# prototype_v2.net
KiCad netlist of a schematic drawn in EAGLE
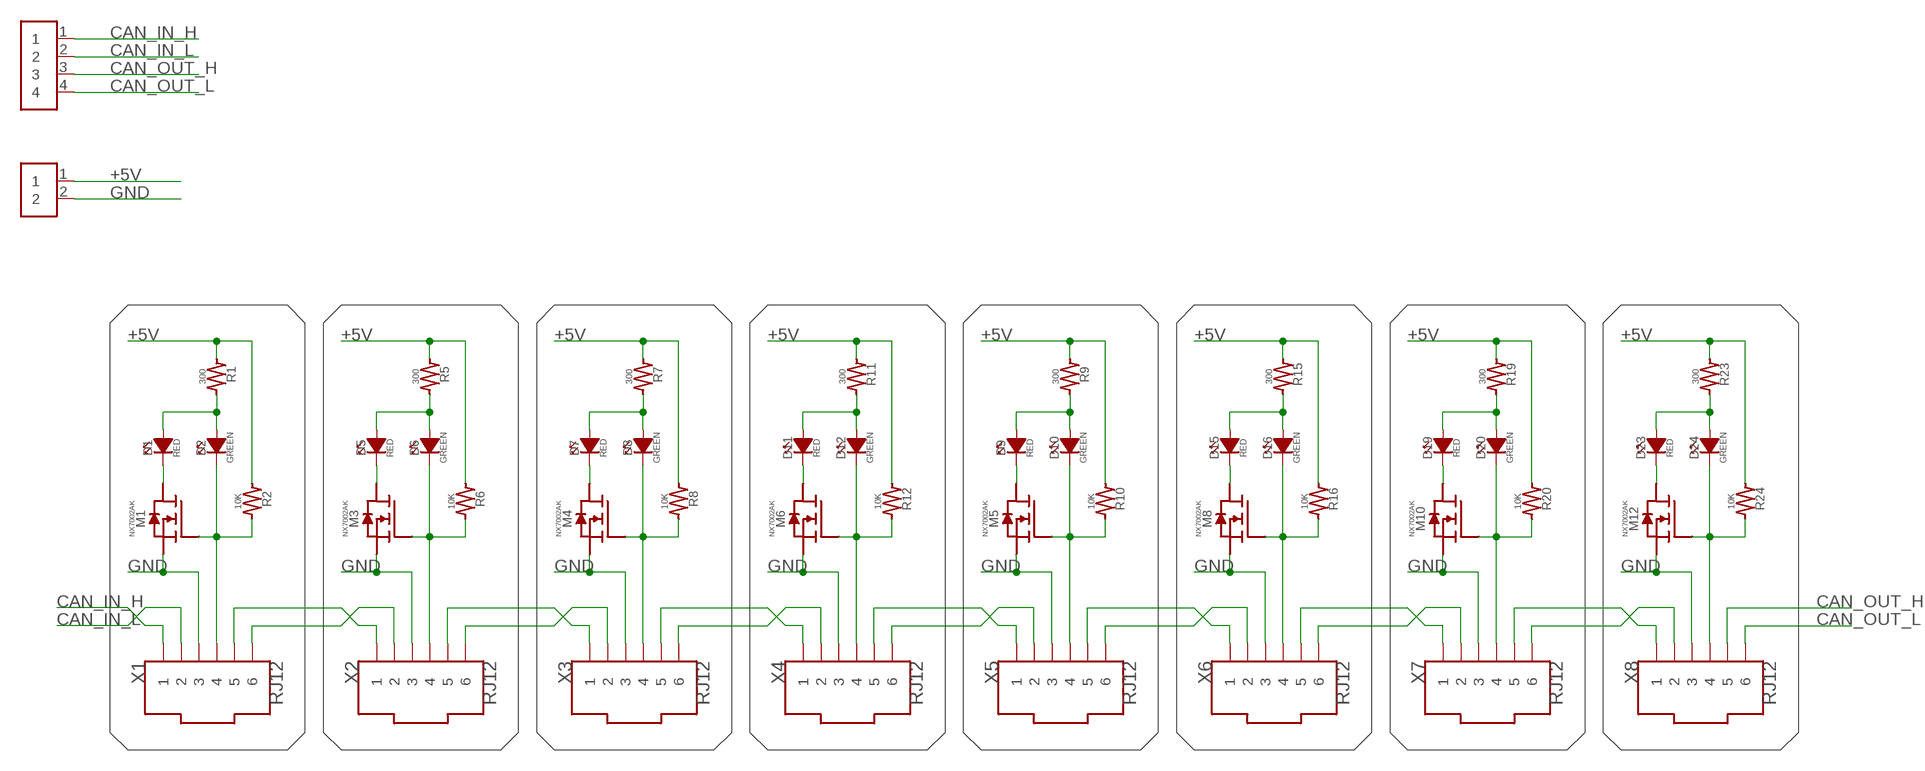
[diagram p0: schematic, sheet 1]

(export (version "E")
  (design (tool "Eeschema 10.0.6"))
  (components
    (comp (ref "D1")
      (value "RED")
      (footprint "eagle-import:0603-LED")
      (libsource (lib "eagle-import") (part "LED"))
    )
    (comp (ref "D2")
      (value "GREEN")
      (footprint "eagle-import:0603-LED")
      (libsource (lib "eagle-import") (part "LED"))
    )
    (comp (ref "D5")
      (value "RED")
      (footprint "eagle-import:0603-LED")
      (libsource (lib "eagle-import") (part "LED"))
    )
    (comp (ref "D6")
      (value "GREEN")
      (footprint "eagle-import:0603-LED")
      (libsource (lib "eagle-import") (part "LED"))
    )
    (comp (ref "D7")
      (value "RED")
      (footprint "eagle-import:0603-LED")
      (libsource (lib "eagle-import") (part "LED"))
    )
    (comp (ref "D8")
      (value "GREEN")
      (footprint "eagle-import:0603-LED")
      (libsource (lib "eagle-import") (part "LED"))
    )
    (comp (ref "D9")
      (value "RED")
      (footprint "eagle-import:0603-LED")
      (libsource (lib "eagle-import") (part "LED"))
    )
    (comp (ref "D10")
      (value "GREEN")
      (footprint "eagle-import:0603-LED")
      (libsource (lib "eagle-import") (part "LED"))
    )
    (comp (ref "D11")
      (value "RED")
      (footprint "eagle-import:0603-LED")
      (libsource (lib "eagle-import") (part "LED"))
    )
    (comp (ref "D12")
      (value "GREEN")
      (footprint "eagle-import:0603-LED")
      (libsource (lib "eagle-import") (part "LED"))
    )
    (comp (ref "D15")
      (value "RED")
      (footprint "eagle-import:0603-LED")
      (libsource (lib "eagle-import") (part "LED"))
    )
    (comp (ref "D16")
      (value "GREEN")
      (footprint "eagle-import:0603-LED")
      (libsource (lib "eagle-import") (part "LED"))
    )
    (comp (ref "D19")
      (value "RED")
      (footprint "eagle-import:0603-LED")
      (libsource (lib "eagle-import") (part "LED"))
    )
    (comp (ref "D20")
      (value "GREEN")
      (footprint "eagle-import:0603-LED")
      (libsource (lib "eagle-import") (part "LED"))
    )
    (comp (ref "D23")
      (value "RED")
      (footprint "eagle-import:0603-LED")
      (libsource (lib "eagle-import") (part "LED"))
    )
    (comp (ref "D24")
      (value "GREEN")
      (footprint "eagle-import:0603-LED")
      (libsource (lib "eagle-import") (part "LED"))
    )
    (comp (ref "M1")
      (value "NX7002AK")
      (footprint "eagle-import:SOT-23")
      (libsource (lib "eagle-import") (part "N-FET"))
    )
    (comp (ref "M3")
      (value "NX7002AK")
      (footprint "eagle-import:SOT-23")
      (libsource (lib "eagle-import") (part "N-FET"))
    )
    (comp (ref "M4")
      (value "NX7002AK")
      (footprint "eagle-import:SOT-23")
      (libsource (lib "eagle-import") (part "N-FET"))
    )
    (comp (ref "M5")
      (value "NX7002AK")
      (footprint "eagle-import:SOT-23")
      (libsource (lib "eagle-import") (part "N-FET"))
    )
    (comp (ref "M6")
      (value "NX7002AK")
      (footprint "eagle-import:SOT-23")
      (libsource (lib "eagle-import") (part "N-FET"))
    )
    (comp (ref "M8")
      (value "NX7002AK")
      (footprint "eagle-import:SOT-23")
      (libsource (lib "eagle-import") (part "N-FET"))
    )
    (comp (ref "M10")
      (value "NX7002AK")
      (footprint "eagle-import:SOT-23")
      (libsource (lib "eagle-import") (part "N-FET"))
    )
    (comp (ref "M12")
      (value "NX7002AK")
      (footprint "eagle-import:SOT-23")
      (libsource (lib "eagle-import") (part "N-FET"))
    )
    (comp (ref "R1")
      (value "300")
      (footprint "eagle-import:0603")
      (libsource (lib "eagle-import") (part "RESISTOR0603"))
    )
    (comp (ref "R2")
      (value "10K")
      (footprint "eagle-import:0603")
      (libsource (lib "eagle-import") (part "RESISTOR0603"))
    )
    (comp (ref "R5")
      (value "300")
      (footprint "eagle-import:0603")
      (libsource (lib "eagle-import") (part "RESISTOR0603"))
    )
    (comp (ref "R6")
      (value "10K")
      (footprint "eagle-import:0603")
      (libsource (lib "eagle-import") (part "RESISTOR0603"))
    )
    (comp (ref "R7")
      (value "300")
      (footprint "eagle-import:0603")
      (libsource (lib "eagle-import") (part "RESISTOR0603"))
    )
    (comp (ref "R8")
      (value "10K")
      (footprint "eagle-import:0603")
      (libsource (lib "eagle-import") (part "RESISTOR0603"))
    )
    (comp (ref "R9")
      (value "300")
      (footprint "eagle-import:0603")
      (libsource (lib "eagle-import") (part "RESISTOR0603"))
    )
    (comp (ref "R10")
      (value "10K")
      (footprint "eagle-import:0603")
      (libsource (lib "eagle-import") (part "RESISTOR0603"))
    )
    (comp (ref "R11")
      (value "300")
      (footprint "eagle-import:0603")
      (libsource (lib "eagle-import") (part "RESISTOR0603"))
    )
    (comp (ref "R12")
      (value "10K")
      (footprint "eagle-import:0603")
      (libsource (lib "eagle-import") (part "RESISTOR0603"))
    )
    (comp (ref "R15")
      (value "300")
      (footprint "eagle-import:0603")
      (libsource (lib "eagle-import") (part "RESISTOR0603"))
    )
    (comp (ref "R16")
      (value "10K")
      (footprint "eagle-import:0603")
      (libsource (lib "eagle-import") (part "RESISTOR0603"))
    )
    (comp (ref "R19")
      (value "300")
      (footprint "eagle-import:0603")
      (libsource (lib "eagle-import") (part "RESISTOR0603"))
    )
    (comp (ref "R20")
      (value "10K")
      (footprint "eagle-import:0603")
      (libsource (lib "eagle-import") (part "RESISTOR0603"))
    )
    (comp (ref "R23")
      (value "300")
      (footprint "eagle-import:0603")
      (libsource (lib "eagle-import") (part "RESISTOR0603"))
    )
    (comp (ref "R24")
      (value "10K")
      (footprint "eagle-import:0603")
      (libsource (lib "eagle-import") (part "RESISTOR0603"))
    )
    (comp (ref "U$1")
      (value "TERMINAL_BLOCK")
      (footprint "eagle-import:TERMINALBLOCK-4")
      (libsource (lib "eagle-import") (part "TERMINAL_BLOCK"))
    )
    (comp (ref "U$2")
      (value "POWER_BLOCK")
      (footprint "eagle-import:TERMINALBLOCK-2")
      (libsource (lib "eagle-import") (part "POWER_BLOCK"))
    )
    (comp (ref "X1")
      (value "RJ12")
      (footprint "eagle-import:RJ12")
      (libsource (lib "eagle-import") (part "RJ12"))
    )
    (comp (ref "X2")
      (value "RJ12")
      (footprint "eagle-import:RJ12")
      (libsource (lib "eagle-import") (part "RJ12"))
    )
    (comp (ref "X3")
      (value "RJ12")
      (footprint "eagle-import:RJ12")
      (libsource (lib "eagle-import") (part "RJ12"))
    )
    (comp (ref "X4")
      (value "RJ12")
      (footprint "eagle-import:RJ12")
      (libsource (lib "eagle-import") (part "RJ12"))
    )
    (comp (ref "X5")
      (value "RJ12")
      (footprint "eagle-import:RJ12")
      (libsource (lib "eagle-import") (part "RJ12"))
    )
    (comp (ref "X6")
      (value "RJ12")
      (footprint "eagle-import:RJ12")
      (libsource (lib "eagle-import") (part "RJ12"))
    )
    (comp (ref "X7")
      (value "RJ12")
      (footprint "eagle-import:RJ12")
      (libsource (lib "eagle-import") (part "RJ12"))
    )
    (comp (ref "X8")
      (value "RJ12")
      (footprint "eagle-import:RJ12")
      (libsource (lib "eagle-import") (part "RJ12"))
    )
  )
  (nets
    (net (code "1") (name "/+5V") (class "Default")
      (node (ref "R1") (pin "1") (pinfunction "1_1") (pintype "bidirectional"))
      (node (ref "R10") (pin "1") (pinfunction "1_1") (pintype "bidirectional"))
      (node (ref "R11") (pin "1") (pinfunction "1_1") (pintype "bidirectional"))
      (node (ref "R12") (pin "1") (pinfunction "1_1") (pintype "bidirectional"))
      (node (ref "R15") (pin "1") (pinfunction "1_1") (pintype "bidirectional"))
      (node (ref "R16") (pin "1") (pinfunction "1_1") (pintype "bidirectional"))
      (node (ref "R19") (pin "1") (pinfunction "1_1") (pintype "bidirectional"))
      (node (ref "R2") (pin "1") (pinfunction "1_1") (pintype "bidirectional"))
      (node (ref "R20") (pin "1") (pinfunction "1_1") (pintype "bidirectional"))
      (node (ref "R23") (pin "1") (pinfunction "1_1") (pintype "bidirectional"))
      (node (ref "R24") (pin "1") (pinfunction "1_1") (pintype "bidirectional"))
      (node (ref "R5") (pin "1") (pinfunction "1_1") (pintype "bidirectional"))
      (node (ref "R6") (pin "1") (pinfunction "1_1") (pintype "bidirectional"))
      (node (ref "R7") (pin "1") (pinfunction "1_1") (pintype "bidirectional"))
      (node (ref "R8") (pin "1") (pinfunction "1_1") (pintype "bidirectional"))
      (node (ref "R9") (pin "1") (pinfunction "1_1") (pintype "bidirectional"))
      (node (ref "U$2") (pin "1") (pinfunction "1_1") (pintype "bidirectional"))
    )
    (net (code "2") (name "/CAN_IN_H") (class "Default")
      (node (ref "U$1") (pin "1") (pinfunction "1_1") (pintype "bidirectional"))
      (node (ref "X1") (pin "1") (pinfunction "1_1") (pintype "bidirectional"))
    )
    (net (code "3") (name "/CAN_IN_L") (class "Default")
      (node (ref "U$1") (pin "2") (pinfunction "2_2") (pintype "bidirectional"))
      (node (ref "X1") (pin "2") (pinfunction "2_2") (pintype "bidirectional"))
    )
    (net (code "4") (name "/CAN_OUT_H") (class "Default")
      (node (ref "U$1") (pin "3") (pinfunction "3_3") (pintype "bidirectional"))
      (node (ref "X8") (pin "5") (pinfunction "5_5") (pintype "bidirectional"))
    )
    (net (code "5") (name "/CAN_OUT_L") (class "Default")
      (node (ref "U$1") (pin "4") (pinfunction "4_4") (pintype "bidirectional"))
      (node (ref "X8") (pin "6") (pinfunction "6_6") (pintype "bidirectional"))
    )
    (net (code "6") (name "/GND") (class "Default")
      (node (ref "M1") (pin "2") (pinfunction "SOURCE_2") (pintype "bidirectional"))
      (node (ref "M10") (pin "2") (pinfunction "SOURCE_2") (pintype "bidirectional"))
      (node (ref "M12") (pin "2") (pinfunction "SOURCE_2") (pintype "bidirectional"))
      (node (ref "M3") (pin "2") (pinfunction "SOURCE_2") (pintype "bidirectional"))
      (node (ref "M4") (pin "2") (pinfunction "SOURCE_2") (pintype "bidirectional"))
      (node (ref "M5") (pin "2") (pinfunction "SOURCE_2") (pintype "bidirectional"))
      (node (ref "M6") (pin "2") (pinfunction "SOURCE_2") (pintype "bidirectional"))
      (node (ref "M8") (pin "2") (pinfunction "SOURCE_2") (pintype "bidirectional"))
      (node (ref "U$2") (pin "2") (pinfunction "2_2") (pintype "bidirectional"))
      (node (ref "X1") (pin "3") (pinfunction "3_3") (pintype "bidirectional"))
      (node (ref "X2") (pin "3") (pinfunction "3_3") (pintype "bidirectional"))
      (node (ref "X3") (pin "3") (pinfunction "3_3") (pintype "bidirectional"))
      (node (ref "X4") (pin "3") (pinfunction "3_3") (pintype "bidirectional"))
      (node (ref "X5") (pin "3") (pinfunction "3_3") (pintype "bidirectional"))
      (node (ref "X6") (pin "3") (pinfunction "3_3") (pintype "bidirectional"))
      (node (ref "X7") (pin "3") (pinfunction "3_3") (pintype "bidirectional"))
      (node (ref "X8") (pin "3") (pinfunction "3_3") (pintype "bidirectional"))
    )
    (net (code "7") (name "Net-(D1-+)") (class "Default")
      (node (ref "D1") (pin "2") (pinfunction "+_2") (pintype "bidirectional"))
      (node (ref "D2") (pin "2") (pinfunction "+_2") (pintype "bidirectional"))
      (node (ref "R1") (pin "2") (pinfunction "2_2") (pintype "bidirectional"))
    )
    (net (code "8") (name "Net-(D1--)") (class "Default")
      (node (ref "D1") (pin "1") (pinfunction "-_1") (pintype "bidirectional"))
      (node (ref "M1") (pin "3") (pinfunction "DRAIN_3") (pintype "bidirectional"))
    )
    (net (code "9") (name "Net-(D2--)") (class "Default")
      (node (ref "D2") (pin "1") (pinfunction "-_1") (pintype "bidirectional"))
      (node (ref "M1") (pin "1") (pinfunction "GATE_1") (pintype "bidirectional"))
      (node (ref "R2") (pin "2") (pinfunction "2_2") (pintype "bidirectional"))
      (node (ref "X1") (pin "4") (pinfunction "4_4") (pintype "bidirectional"))
    )
    (net (code "10") (name "Net-(D5-+)") (class "Default")
      (node (ref "D5") (pin "2") (pinfunction "+_2") (pintype "bidirectional"))
      (node (ref "D6") (pin "2") (pinfunction "+_2") (pintype "bidirectional"))
      (node (ref "R5") (pin "2") (pinfunction "2_2") (pintype "bidirectional"))
    )
    (net (code "11") (name "Net-(D5--)") (class "Default")
      (node (ref "D5") (pin "1") (pinfunction "-_1") (pintype "bidirectional"))
      (node (ref "M3") (pin "3") (pinfunction "DRAIN_3") (pintype "bidirectional"))
    )
    (net (code "12") (name "Net-(D6--)") (class "Default")
      (node (ref "D6") (pin "1") (pinfunction "-_1") (pintype "bidirectional"))
      (node (ref "M3") (pin "1") (pinfunction "GATE_1") (pintype "bidirectional"))
      (node (ref "R6") (pin "2") (pinfunction "2_2") (pintype "bidirectional"))
      (node (ref "X2") (pin "4") (pinfunction "4_4") (pintype "bidirectional"))
    )
    (net (code "13") (name "Net-(D7-+)") (class "Default")
      (node (ref "D7") (pin "2") (pinfunction "+_2") (pintype "bidirectional"))
      (node (ref "D8") (pin "2") (pinfunction "+_2") (pintype "bidirectional"))
      (node (ref "R7") (pin "2") (pinfunction "2_2") (pintype "bidirectional"))
    )
    (net (code "14") (name "Net-(D7--)") (class "Default")
      (node (ref "D7") (pin "1") (pinfunction "-_1") (pintype "bidirectional"))
      (node (ref "M4") (pin "3") (pinfunction "DRAIN_3") (pintype "bidirectional"))
    )
    (net (code "15") (name "Net-(D8--)") (class "Default")
      (node (ref "D8") (pin "1") (pinfunction "-_1") (pintype "bidirectional"))
      (node (ref "M4") (pin "1") (pinfunction "GATE_1") (pintype "bidirectional"))
      (node (ref "R8") (pin "2") (pinfunction "2_2") (pintype "bidirectional"))
      (node (ref "X3") (pin "4") (pinfunction "4_4") (pintype "bidirectional"))
    )
    (net (code "16") (name "Net-(D9--)") (class "Default")
      (node (ref "D9") (pin "1") (pinfunction "-_1") (pintype "bidirectional"))
      (node (ref "M5") (pin "3") (pinfunction "DRAIN_3") (pintype "bidirectional"))
    )
    (net (code "17") (name "Net-(D10-+)") (class "Default")
      (node (ref "D10") (pin "2") (pinfunction "+_2") (pintype "bidirectional"))
      (node (ref "D9") (pin "2") (pinfunction "+_2") (pintype "bidirectional"))
      (node (ref "R9") (pin "2") (pinfunction "2_2") (pintype "bidirectional"))
    )
    (net (code "18") (name "Net-(D10--)") (class "Default")
      (node (ref "D10") (pin "1") (pinfunction "-_1") (pintype "bidirectional"))
      (node (ref "M5") (pin "1") (pinfunction "GATE_1") (pintype "bidirectional"))
      (node (ref "R10") (pin "2") (pinfunction "2_2") (pintype "bidirectional"))
      (node (ref "X5") (pin "4") (pinfunction "4_4") (pintype "bidirectional"))
    )
    (net (code "19") (name "Net-(D11-+)") (class "Default")
      (node (ref "D11") (pin "2") (pinfunction "+_2") (pintype "bidirectional"))
      (node (ref "D12") (pin "2") (pinfunction "+_2") (pintype "bidirectional"))
      (node (ref "R11") (pin "2") (pinfunction "2_2") (pintype "bidirectional"))
    )
    (net (code "20") (name "Net-(D11--)") (class "Default")
      (node (ref "D11") (pin "1") (pinfunction "-_1") (pintype "bidirectional"))
      (node (ref "M6") (pin "3") (pinfunction "DRAIN_3") (pintype "bidirectional"))
    )
    (net (code "21") (name "Net-(D12--)") (class "Default")
      (node (ref "D12") (pin "1") (pinfunction "-_1") (pintype "bidirectional"))
      (node (ref "M6") (pin "1") (pinfunction "GATE_1") (pintype "bidirectional"))
      (node (ref "R12") (pin "2") (pinfunction "2_2") (pintype "bidirectional"))
      (node (ref "X4") (pin "4") (pinfunction "4_4") (pintype "bidirectional"))
    )
    (net (code "22") (name "Net-(D15-+)") (class "Default")
      (node (ref "D15") (pin "2") (pinfunction "+_2") (pintype "bidirectional"))
      (node (ref "D16") (pin "2") (pinfunction "+_2") (pintype "bidirectional"))
      (node (ref "R15") (pin "2") (pinfunction "2_2") (pintype "bidirectional"))
    )
    (net (code "23") (name "Net-(D15--)") (class "Default")
      (node (ref "D15") (pin "1") (pinfunction "-_1") (pintype "bidirectional"))
      (node (ref "M8") (pin "3") (pinfunction "DRAIN_3") (pintype "bidirectional"))
    )
    (net (code "24") (name "Net-(D16--)") (class "Default")
      (node (ref "D16") (pin "1") (pinfunction "-_1") (pintype "bidirectional"))
      (node (ref "M8") (pin "1") (pinfunction "GATE_1") (pintype "bidirectional"))
      (node (ref "R16") (pin "2") (pinfunction "2_2") (pintype "bidirectional"))
      (node (ref "X6") (pin "4") (pinfunction "4_4") (pintype "bidirectional"))
    )
    (net (code "25") (name "Net-(D19-+)") (class "Default")
      (node (ref "D19") (pin "2") (pinfunction "+_2") (pintype "bidirectional"))
      (node (ref "D20") (pin "2") (pinfunction "+_2") (pintype "bidirectional"))
      (node (ref "R19") (pin "2") (pinfunction "2_2") (pintype "bidirectional"))
    )
    (net (code "26") (name "Net-(D19--)") (class "Default")
      (node (ref "D19") (pin "1") (pinfunction "-_1") (pintype "bidirectional"))
      (node (ref "M10") (pin "3") (pinfunction "DRAIN_3") (pintype "bidirectional"))
    )
    (net (code "27") (name "Net-(D20--)") (class "Default")
      (node (ref "D20") (pin "1") (pinfunction "-_1") (pintype "bidirectional"))
      (node (ref "M10") (pin "1") (pinfunction "GATE_1") (pintype "bidirectional"))
      (node (ref "R20") (pin "2") (pinfunction "2_2") (pintype "bidirectional"))
      (node (ref "X7") (pin "4") (pinfunction "4_4") (pintype "bidirectional"))
    )
    (net (code "28") (name "Net-(D23-+)") (class "Default")
      (node (ref "D23") (pin "2") (pinfunction "+_2") (pintype "bidirectional"))
      (node (ref "D24") (pin "2") (pinfunction "+_2") (pintype "bidirectional"))
      (node (ref "R23") (pin "2") (pinfunction "2_2") (pintype "bidirectional"))
    )
    (net (code "29") (name "Net-(D23--)") (class "Default")
      (node (ref "D23") (pin "1") (pinfunction "-_1") (pintype "bidirectional"))
      (node (ref "M12") (pin "3") (pinfunction "DRAIN_3") (pintype "bidirectional"))
    )
    (net (code "30") (name "Net-(D24--)") (class "Default")
      (node (ref "D24") (pin "1") (pinfunction "-_1") (pintype "bidirectional"))
      (node (ref "M12") (pin "1") (pinfunction "GATE_1") (pintype "bidirectional"))
      (node (ref "R24") (pin "2") (pinfunction "2_2") (pintype "bidirectional"))
      (node (ref "X8") (pin "4") (pinfunction "4_4") (pintype "bidirectional"))
    )
    (net (code "31") (name "Net-(X1-Pad5)") (class "Default")
      (node (ref "X1") (pin "5") (pinfunction "5_5") (pintype "bidirectional"))
      (node (ref "X2") (pin "1") (pinfunction "1_1") (pintype "bidirectional"))
    )
    (net (code "32") (name "Net-(X1-Pad6)") (class "Default")
      (node (ref "X1") (pin "6") (pinfunction "6_6") (pintype "bidirectional"))
      (node (ref "X2") (pin "2") (pinfunction "2_2") (pintype "bidirectional"))
    )
    (net (code "33") (name "Net-(X2-Pad5)") (class "Default")
      (node (ref "X2") (pin "5") (pinfunction "5_5") (pintype "bidirectional"))
      (node (ref "X3") (pin "1") (pinfunction "1_1") (pintype "bidirectional"))
    )
    (net (code "34") (name "Net-(X2-Pad6)") (class "Default")
      (node (ref "X2") (pin "6") (pinfunction "6_6") (pintype "bidirectional"))
      (node (ref "X3") (pin "2") (pinfunction "2_2") (pintype "bidirectional"))
    )
    (net (code "35") (name "Net-(X3-Pad5)") (class "Default")
      (node (ref "X3") (pin "5") (pinfunction "5_5") (pintype "bidirectional"))
      (node (ref "X4") (pin "1") (pinfunction "1_1") (pintype "bidirectional"))
    )
    (net (code "36") (name "Net-(X3-Pad6)") (class "Default")
      (node (ref "X3") (pin "6") (pinfunction "6_6") (pintype "bidirectional"))
      (node (ref "X4") (pin "2") (pinfunction "2_2") (pintype "bidirectional"))
    )
    (net (code "37") (name "Net-(X4-Pad5)") (class "Default")
      (node (ref "X4") (pin "5") (pinfunction "5_5") (pintype "bidirectional"))
      (node (ref "X5") (pin "1") (pinfunction "1_1") (pintype "bidirectional"))
    )
    (net (code "38") (name "Net-(X4-Pad6)") (class "Default")
      (node (ref "X4") (pin "6") (pinfunction "6_6") (pintype "bidirectional"))
      (node (ref "X5") (pin "2") (pinfunction "2_2") (pintype "bidirectional"))
    )
    (net (code "39") (name "Net-(X5-Pad5)") (class "Default")
      (node (ref "X5") (pin "5") (pinfunction "5_5") (pintype "bidirectional"))
      (node (ref "X6") (pin "1") (pinfunction "1_1") (pintype "bidirectional"))
    )
    (net (code "40") (name "Net-(X5-Pad6)") (class "Default")
      (node (ref "X5") (pin "6") (pinfunction "6_6") (pintype "bidirectional"))
      (node (ref "X6") (pin "2") (pinfunction "2_2") (pintype "bidirectional"))
    )
    (net (code "41") (name "Net-(X6-Pad5)") (class "Default")
      (node (ref "X6") (pin "5") (pinfunction "5_5") (pintype "bidirectional"))
      (node (ref "X7") (pin "1") (pinfunction "1_1") (pintype "bidirectional"))
    )
    (net (code "42") (name "Net-(X6-Pad6)") (class "Default")
      (node (ref "X6") (pin "6") (pinfunction "6_6") (pintype "bidirectional"))
      (node (ref "X7") (pin "2") (pinfunction "2_2") (pintype "bidirectional"))
    )
    (net (code "43") (name "Net-(X7-Pad5)") (class "Default")
      (node (ref "X7") (pin "5") (pinfunction "5_5") (pintype "bidirectional"))
      (node (ref "X8") (pin "1") (pinfunction "1_1") (pintype "bidirectional"))
    )
    (net (code "44") (name "Net-(X7-Pad6)") (class "Default")
      (node (ref "X7") (pin "6") (pinfunction "6_6") (pintype "bidirectional"))
      (node (ref "X8") (pin "2") (pinfunction "2_2") (pintype "bidirectional"))
    )
  )
)
